# electricals_with_iPod_v2_6.net
KiCad netlist of a schematic drawn in EAGLE
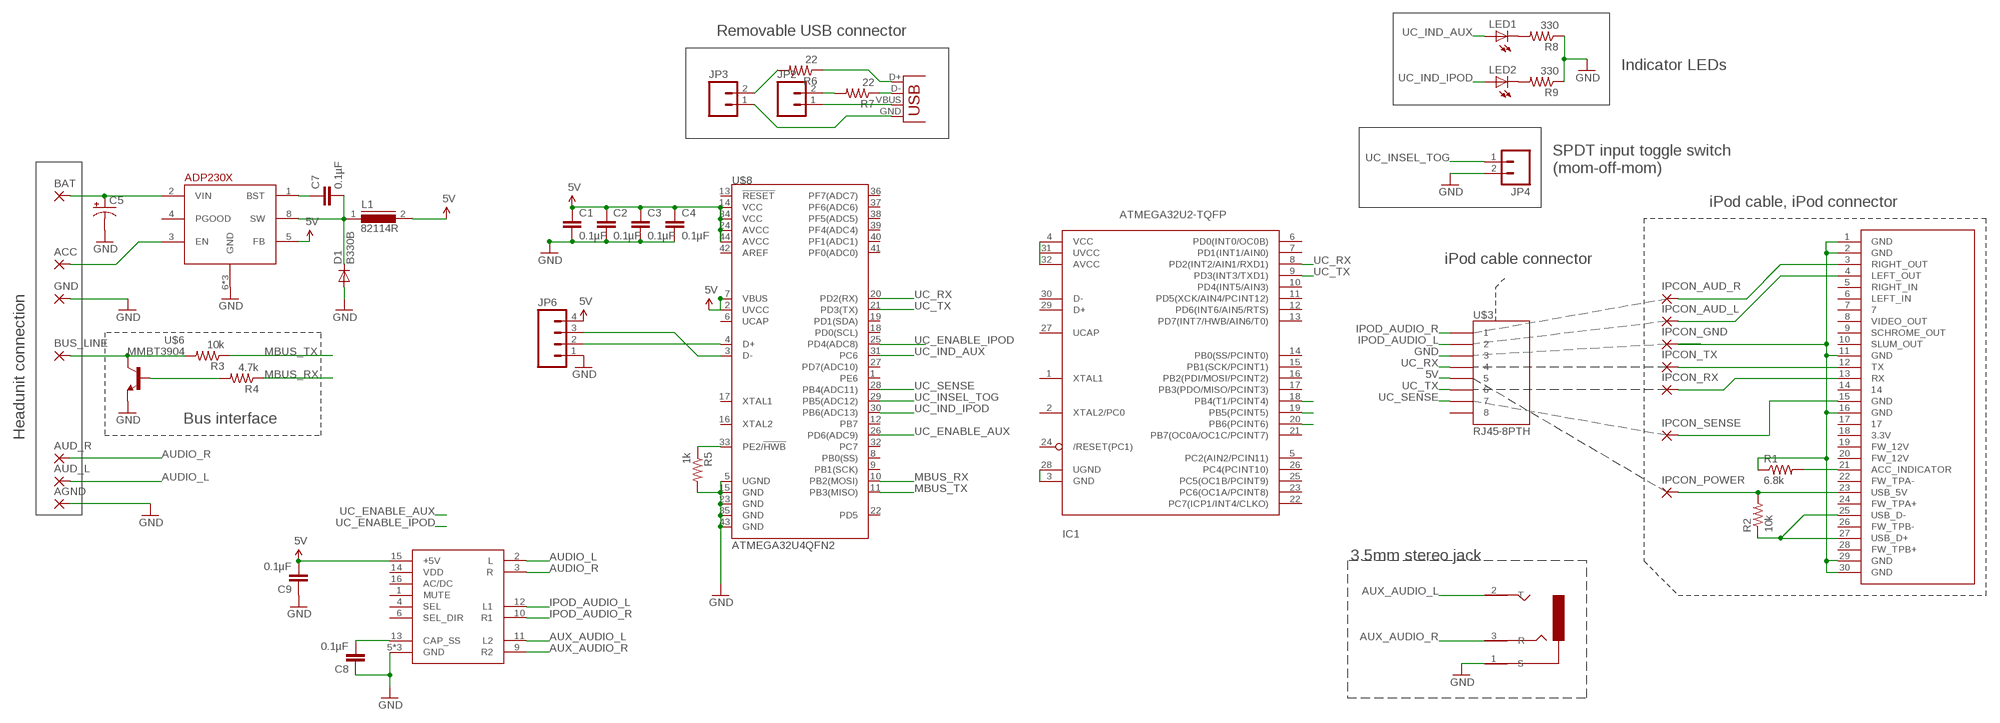
[diagram p0: schematic, sheet 1]

(export (version "E")
  (design (tool "Eeschema 10.0.6"))
  (components
    (comp (ref "ACC")
      (value "1,6/0,9")
      (footprint "eagle-import:1,6_0,9")
      (libsource (lib "eagle-import") (part "1,6/0,9"))
    )
    (comp (ref "AGND")
      (value "1,6/0,9")
      (footprint "eagle-import:1,6_0,9")
      (libsource (lib "eagle-import") (part "1,6/0,9"))
    )
    (comp (ref "AUD_L")
      (value "1,6/0,9")
      (footprint "eagle-import:1,6_0,9")
      (libsource (lib "eagle-import") (part "1,6/0,9"))
    )
    (comp (ref "AUD_R")
      (value "1,6/0,9")
      (footprint "eagle-import:1,6_0,9")
      (libsource (lib "eagle-import") (part "1,6/0,9"))
    )
    (comp (ref "BAT")
      (value "2,54/1,1")
      (footprint "eagle-import:2,54_1,1")
      (libsource (lib "eagle-import") (part "2,54/1,1"))
    )
    (comp (ref "BUS_LINE")
      (value "1,6/0,9")
      (footprint "eagle-import:1,6_0,9")
      (libsource (lib "eagle-import") (part "1,6/0,9"))
    )
    (comp (ref "C1")
      (value "0.1µF")
      (footprint "eagle-import:0603-CAP")
      (libsource (lib "eagle-import") (part "CAP0603-CAP"))
    )
    (comp (ref "C2")
      (value "0.1µF")
      (footprint "eagle-import:0603-CAP")
      (libsource (lib "eagle-import") (part "CAP0603-CAP"))
    )
    (comp (ref "C3")
      (value "0.1µF")
      (footprint "eagle-import:0603-CAP")
      (libsource (lib "eagle-import") (part "CAP0603-CAP"))
    )
    (comp (ref "C4")
      (value "0.1µF")
      (footprint "eagle-import:0603-CAP")
      (libsource (lib "eagle-import") (part "CAP0603-CAP"))
    )
    (comp (ref "C5")
      (value "CAP_POLPTH2")
      (footprint "eagle-import:CPOL-RADIAL-10UF-25V")
      (libsource (lib "eagle-import") (part "CAP_POLPTH2"))
    )
    (comp (ref "C7")
      (value "0.1µF")
      (footprint "eagle-import:0603-CAP")
      (libsource (lib "eagle-import") (part "CAP0603-CAP"))
    )
    (comp (ref "C8")
      (value "0.1µF")
      (footprint "eagle-import:0603-CAP")
      (libsource (lib "eagle-import") (part "CAP0603-CAP"))
    )
    (comp (ref "C9")
      (value "0.1µF")
      (footprint "eagle-import:0603-CAP")
      (libsource (lib "eagle-import") (part "CAP0603-CAP"))
    )
    (comp (ref "D1")
      (value "B330B")
      (footprint "eagle-import:SMA-DIODE_ALT")
      (libsource (lib "eagle-import") (part "DIODESMA-ALT"))
    )
    (comp (ref "GND")
      (value "2,54/1,1")
      (footprint "eagle-import:2,54_1,1")
      (libsource (lib "eagle-import") (part "2,54/1,1"))
    )
    (comp (ref "IC1")
      (value "ATMEGA32U2-TQFP")
      (footprint "eagle-import:TQFP32-08")
      (libsource (lib "eagle-import") (part "ATMEGA32U2-TQFP"))
    )
    (comp (ref "IPCON_AUD_L")
      (value "1,6/0,9")
      (footprint "eagle-import:1,6_0,9")
      (libsource (lib "eagle-import") (part "1,6/0,9"))
    )
    (comp (ref "IPCON_AUD_R")
      (value "1,6/0,9")
      (footprint "eagle-import:1,6_0,9")
      (libsource (lib "eagle-import") (part "1,6/0,9"))
    )
    (comp (ref "IPCON_GND")
      (value "1,6/0,9")
      (footprint "eagle-import:1,6_0,9")
      (libsource (lib "eagle-import") (part "1,6/0,9"))
    )
    (comp (ref "IPCON_POWER")
      (value "1,6/0,9")
      (footprint "eagle-import:1,6_0,9")
      (libsource (lib "eagle-import") (part "1,6/0,9"))
    )
    (comp (ref "IPCON_RX")
      (value "1,6/0,9")
      (footprint "eagle-import:1,6_0,9")
      (libsource (lib "eagle-import") (part "1,6/0,9"))
    )
    (comp (ref "IPCON_SENSE")
      (value "1,6/0,9")
      (footprint "eagle-import:1,6_0,9")
      (libsource (lib "eagle-import") (part "1,6/0,9"))
    )
    (comp (ref "IPCON_TX")
      (value "1,6/0,9")
      (footprint "eagle-import:1,6_0,9")
      (libsource (lib "eagle-import") (part "1,6/0,9"))
    )
    (comp (ref "JP1")
      (value "USBSMD")
      (footprint "eagle-import:USB-MINIB")
      (libsource (lib "eagle-import") (part "USBSMD"))
    )
    (comp (ref "JP2")
      (value "M02POGO_PIN_HOLES_ONLY")
      (footprint "eagle-import:1X02_PP_HOLES_ONLY")
      (libsource (lib "eagle-import") (part "M02POGO_PIN_HOLES_ONLY"))
    )
    (comp (ref "JP3")
      (value "M02POGO_PIN_HOLES_ONLY")
      (footprint "eagle-import:1X02_PP_HOLES_ONLY")
      (libsource (lib "eagle-import") (part "M02POGO_PIN_HOLES_ONLY"))
    )
    (comp (ref "JP4")
      (value "M02LOCK")
      (footprint "eagle-import:1X02_LOCK")
      (libsource (lib "eagle-import") (part "M02LOCK"))
    )
    (comp (ref "JP6")
      (value "M04PTH")
      (footprint "eagle-import:1X04")
      (libsource (lib "eagle-import") (part "M04PTH"))
    )
    (comp (ref "L1")
      (value "82114R")
      (footprint "eagle-import:82114R")
      (libsource (lib "eagle-import") (part "82114R"))
    )
    (comp (ref "LED1")
      (value "LED0603")
      (footprint "eagle-import:LED-0603")
      (libsource (lib "eagle-import") (part "LED0603"))
    )
    (comp (ref "LED2")
      (value "LED0603")
      (footprint "eagle-import:LED-0603")
      (libsource (lib "eagle-import") (part "LED0603"))
    )
    (comp (ref "R1")
      (value "6.8k")
      (footprint "eagle-import:0603-RES")
      (libsource (lib "eagle-import") (part "RESISTOR0603-RES"))
    )
    (comp (ref "R2")
      (value "10k")
      (footprint "eagle-import:0603-RES")
      (libsource (lib "eagle-import") (part "RESISTOR0603-RES"))
    )
    (comp (ref "R3")
      (value "10k")
      (footprint "eagle-import:0603-RES")
      (libsource (lib "eagle-import") (part "RESISTOR0603-RES"))
    )
    (comp (ref "R4")
      (value "4.7k")
      (footprint "eagle-import:0603-RES")
      (libsource (lib "eagle-import") (part "RESISTOR0603-RES"))
    )
    (comp (ref "R5")
      (value "1k")
      (footprint "eagle-import:0603-RES")
      (libsource (lib "eagle-import") (part "RESISTOR0603-RES"))
    )
    (comp (ref "R6")
      (value "22")
      (footprint "eagle-import:0603-RES")
      (libsource (lib "eagle-import") (part "RESISTOR0603-RES"))
    )
    (comp (ref "R7")
      (value "22")
      (footprint "eagle-import:0603-RES")
      (libsource (lib "eagle-import") (part "RESISTOR0603-RES"))
    )
    (comp (ref "R8")
      (value "330")
      (footprint "eagle-import:0603-RES")
      (libsource (lib "eagle-import") (part "RESISTOR0603-RES"))
    )
    (comp (ref "R9")
      (value "330")
      (footprint "eagle-import:0603-RES")
      (libsource (lib "eagle-import") (part "RESISTOR0603-RES"))
    )
    (comp (ref "U$1")
      (value "IPOD_CONNECTOR_MALE")
      (footprint "eagle-import:IPOD_MALE_CONNECTOR")
      (libsource (lib "eagle-import") (part "IPOD_CONNECTOR_MALE"))
    )
    (comp (ref "U$3")
      (value "RJ45-8PTH")
      (footprint "eagle-import:RJ45-8")
      (libsource (lib "eagle-import") (part "RJ45-8PTH"))
    )
    (comp (ref "U$5")
      (value "ADP230X")
      (footprint "eagle-import:SO8-THERM")
      (libsource (lib "eagle-import") (part "ADP230X"))
    )
    (comp (ref "U$6")
      (value "MMBT3904")
      (footprint "eagle-import:SOT23-3")
      (libsource (lib "eagle-import") (part "MMBT3904"))
    )
    (comp (ref "U$7")
      (value "STEREO_JACK_SJ1-353XNG3NG")
      (footprint "eagle-import:3.5MM_SJ1-353XNG")
      (libsource (lib "eagle-import") (part "STEREO_JACK_SJ1-353XNG3NG"))
    )
    (comp (ref "U$8")
      (value "ATMEGA32U4QFN2")
      (footprint "eagle-import:SPARKFUN-DIGITALIC_QFN-44-NOPAD")
      (libsource (lib "eagle-import") (part "ATMEGA32U4QFN2"))
    )
    (comp (ref "U$11")
      (value "ISL54405IRTZ")
      (footprint "eagle-import:QFN-16")
      (libsource (lib "eagle-import") (part "ISL54405IRTZ"))
    )
  )
  (nets
    (net (code "1") (name "/AUDIO_L") (class "Default")
      (node (ref "AUD_L") (pin "1") (pinfunction "P_1") (pintype "passive"))
      (node (ref "U$11") (pin "2") (pinfunction "L_2") (pintype "bidirectional"))
    )
    (net (code "2") (name "/AUDIO_R") (class "Default")
      (node (ref "AUD_R") (pin "1") (pinfunction "P_1") (pintype "passive"))
      (node (ref "U$11") (pin "3") (pinfunction "R_3") (pintype "bidirectional"))
    )
    (net (code "3") (name "/AUX_AUDIO_L") (class "Default")
      (node (ref "U$11") (pin "11") (pinfunction "L2_11") (pintype "bidirectional"))
      (node (ref "U$7") (pin "2") (pinfunction "T_2") (pintype "passive"))
    )
    (net (code "4") (name "/AUX_AUDIO_R") (class "Default")
      (node (ref "U$11") (pin "9") (pinfunction "R2_9") (pintype "bidirectional"))
      (node (ref "U$7") (pin "3") (pinfunction "R_3") (pintype "passive"))
    )
    (net (code "5") (name "/IPOD_AUDIO_L") (class "Default")
      (node (ref "U$11") (pin "12") (pinfunction "L1_12") (pintype "bidirectional"))
      (node (ref "U$3") (pin "2") (pinfunction "2_2") (pintype "bidirectional"))
    )
    (net (code "6") (name "/IPOD_AUDIO_R") (class "Default")
      (node (ref "U$11") (pin "10") (pinfunction "R1_10") (pintype "bidirectional"))
      (node (ref "U$3") (pin "1") (pinfunction "1_1") (pintype "bidirectional"))
    )
    (net (code "7") (name "/MBUS_RX") (class "Default")
      (node (ref "R4") (pin "1") (pinfunction "1_1") (pintype "passive"))
      (node (ref "U$8") (pin "10") (pinfunction "PB2(MOSI)_10") (pintype "bidirectional"))
    )
    (net (code "8") (name "/MBUS_TX") (class "Default")
      (node (ref "R3") (pin "1") (pinfunction "1_1") (pintype "passive"))
      (node (ref "U$8") (pin "11") (pinfunction "PB3(MISO)_11") (pintype "bidirectional"))
    )
    (net (code "9") (name "/UC_ENABLE_AUX") (class "Default")
      (node (ref "U$8") (pin "26") (pinfunction "PD6(ADC9)_26") (pintype "bidirectional"))
    )
    (net (code "10") (name "/UC_ENABLE_IPOD") (class "Default")
      (node (ref "U$8") (pin "25") (pinfunction "PD4(ADC8)_25") (pintype "bidirectional"))
    )
    (net (code "11") (name "/UC_IND_AUX") (class "Default")
      (node (ref "LED1") (pin "A") (pinfunction "A_A") (pintype "passive"))
      (node (ref "U$8") (pin "31") (pinfunction "PC6_31") (pintype "bidirectional"))
    )
    (net (code "12") (name "/UC_IND_IPOD") (class "Default")
      (node (ref "LED2") (pin "A") (pinfunction "A_A") (pintype "passive"))
      (node (ref "U$8") (pin "30") (pinfunction "PB6(ADC13)_30") (pintype "bidirectional"))
    )
    (net (code "13") (name "/UC_INSEL_TOG") (class "Default")
      (node (ref "JP4") (pin "1") (pinfunction "1_1") (pintype "passive"))
      (node (ref "U$8") (pin "29") (pinfunction "PB5(ADC12)_29") (pintype "bidirectional"))
    )
    (net (code "14") (name "/UC_RX") (class "Default")
      (node (ref "IC1") (pin "8") (pinfunction "PD2(INT2/AIN1/RXD1)_8") (pintype "bidirectional"))
      (node (ref "U$3") (pin "4") (pinfunction "4_4") (pintype "bidirectional"))
      (node (ref "U$8") (pin "20") (pinfunction "PD2(RX)_20") (pintype "bidirectional"))
    )
    (net (code "15") (name "/UC_SENSE") (class "Default")
      (node (ref "U$3") (pin "7") (pinfunction "7_7") (pintype "bidirectional"))
      (node (ref "U$8") (pin "28") (pinfunction "PB4(ADC11)_28") (pintype "bidirectional"))
    )
    (net (code "16") (name "/UC_TX") (class "Default")
      (node (ref "IC1") (pin "9") (pinfunction "PD3(INT3/TXD1)_9") (pintype "bidirectional"))
      (node (ref "U$3") (pin "6") (pinfunction "6_6") (pintype "bidirectional"))
      (node (ref "U$8") (pin "21") (pinfunction "PD3(TX)_21") (pintype "bidirectional"))
    )
    (net (code "17") (name "5V") (class "Default")
      (node (ref "C1") (pin "1") (pinfunction "1_1") (pintype "passive"))
      (node (ref "C2") (pin "1") (pinfunction "1_1") (pintype "passive"))
      (node (ref "C3") (pin "1") (pinfunction "1_1") (pintype "passive"))
      (node (ref "C4") (pin "1") (pinfunction "1_1") (pintype "passive"))
      (node (ref "C9") (pin "2") (pinfunction "2_2") (pintype "passive"))
      (node (ref "JP6") (pin "4") (pinfunction "4_4") (pintype "passive"))
      (node (ref "L1") (pin "2") (pinfunction "2_2") (pintype "passive"))
      (node (ref "U$11") (pin "15") (pinfunction "+5V_15") (pintype "bidirectional"))
      (node (ref "U$3") (pin "5") (pinfunction "5_5") (pintype "bidirectional"))
      (node (ref "U$5") (pin "5") (pinfunction "FB_5") (pintype "bidirectional"))
      (node (ref "U$8") (pin "14") (pinfunction "VCC_14") (pintype "bidirectional"))
      (node (ref "U$8") (pin "2") (pinfunction "UVCC_2") (pintype "bidirectional"))
      (node (ref "U$8") (pin "24") (pinfunction "AVCC_24") (pintype "bidirectional"))
      (node (ref "U$8") (pin "34") (pinfunction "VCC_34") (pintype "bidirectional"))
      (node (ref "U$8") (pin "44") (pinfunction "AVCC_44") (pintype "bidirectional"))
      (node (ref "U$8") (pin "7") (pinfunction "VBUS_7") (pintype "bidirectional"))
    )
    (net (code "18") (name "GND") (class "Default")
      (node (ref "AGND") (pin "1") (pinfunction "P_1") (pintype "passive"))
      (node (ref "C1") (pin "2") (pinfunction "2_2") (pintype "passive"))
      (node (ref "C2") (pin "2") (pinfunction "2_2") (pintype "passive"))
      (node (ref "C3") (pin "2") (pinfunction "2_2") (pintype "passive"))
      (node (ref "C4") (pin "2") (pinfunction "2_2") (pintype "passive"))
      (node (ref "C5") (pin "2") (pinfunction "-_2") (pintype "passive"))
      (node (ref "C8") (pin "1") (pinfunction "1_1") (pintype "passive"))
      (node (ref "C9") (pin "1") (pinfunction "1_1") (pintype "passive"))
      (node (ref "D1") (pin "A") (pinfunction "A_A") (pintype "passive"))
      (node (ref "GND") (pin "1") (pinfunction "P_1") (pintype "passive"))
      (node (ref "JP4") (pin "2") (pinfunction "2_2") (pintype "passive"))
      (node (ref "JP6") (pin "1") (pinfunction "1_1") (pintype "passive"))
      (node (ref "R5") (pin "2") (pinfunction "2_2") (pintype "passive"))
      (node (ref "R8") (pin "1") (pinfunction "1_1") (pintype "passive"))
      (node (ref "R9") (pin "1") (pinfunction "1_1") (pintype "passive"))
      (node (ref "U$11") (pin "5") (pinfunction "GND_5") (pintype "bidirectional"))
      (node (ref "U$11") (pin "7") (pinfunction "GND_7") (pintype "bidirectional"))
      (node (ref "U$11") (pin "8") (pinfunction "GND_8") (pintype "bidirectional"))
      (node (ref "U$3") (pin "3") (pinfunction "3_3") (pintype "bidirectional"))
      (node (ref "U$5") (pin "6") (pinfunction "GND_6") (pintype "bidirectional"))
      (node (ref "U$5") (pin "7") (pinfunction "GND_7") (pintype "bidirectional"))
      (node (ref "U$5") (pin "PAD") (pinfunction "GND_PAD") (pintype "bidirectional"))
      (node (ref "U$6") (pin "2") (pinfunction "E_2") (pintype "passive"))
      (node (ref "U$7") (pin "1") (pinfunction "S_1") (pintype "passive"))
      (node (ref "U$8") (pin "15") (pinfunction "GND_15") (pintype "bidirectional"))
      (node (ref "U$8") (pin "23") (pinfunction "GND_23") (pintype "bidirectional"))
      (node (ref "U$8") (pin "35") (pinfunction "GND_35") (pintype "bidirectional"))
      (node (ref "U$8") (pin "43") (pinfunction "GND_43") (pintype "bidirectional"))
      (node (ref "U$8") (pin "5") (pinfunction "UGND_5") (pintype "bidirectional"))
    )
    (net (code "19") (name "Net-(ACC-P)") (class "Default")
      (node (ref "ACC") (pin "1") (pinfunction "P_1") (pintype "passive"))
      (node (ref "U$5") (pin "3") (pinfunction "EN_3") (pintype "bidirectional"))
    )
    (net (code "20") (name "Net-(BAT-P)") (class "Default")
      (node (ref "BAT") (pin "1") (pinfunction "P_1") (pintype "passive"))
      (node (ref "C5") (pin "1") (pinfunction "+_1") (pintype "passive"))
      (node (ref "U$5") (pin "2") (pinfunction "VIN_2") (pintype "bidirectional"))
    )
    (net (code "21") (name "Net-(BUS_LINE-P)") (class "Default")
      (node (ref "BUS_LINE") (pin "1") (pinfunction "P_1") (pintype "passive"))
      (node (ref "R3") (pin "2") (pinfunction "2_2") (pintype "passive"))
      (node (ref "U$6") (pin "3") (pinfunction "C_3") (pintype "passive"))
    )
    (net (code "22") (name "Net-(IC1-AVCC)") (class "Default")
      (node (ref "IC1") (pin "32") (pinfunction "AVCC_32") (pintype "bidirectional"))
      (node (ref "IC1") (pin "4") (pinfunction "VCC_4") (pintype "bidirectional"))
    )
    (net (code "23") (name "Net-(IC1-GND)") (class "Default")
      (node (ref "IC1") (pin "28") (pinfunction "UGND_28") (pintype "bidirectional"))
      (node (ref "IC1") (pin "3") (pinfunction "GND_3") (pintype "bidirectional"))
    )
    (net (code "24") (name "Net-(IPCON_AUD_L-P)") (class "Default")
      (node (ref "IPCON_AUD_L") (pin "1") (pinfunction "P_1") (pintype "passive"))
      (node (ref "U$1") (pin "4") (pinfunction "LEFT_OUT_4") (pintype "bidirectional"))
    )
    (net (code "25") (name "Net-(IPCON_AUD_R-P)") (class "Default")
      (node (ref "IPCON_AUD_R") (pin "1") (pinfunction "P_1") (pintype "passive"))
      (node (ref "U$1") (pin "3") (pinfunction "RIGHT_OUT_3") (pintype "bidirectional"))
    )
    (net (code "26") (name "Net-(IPCON_GND-P)") (class "Default")
      (node (ref "IPCON_GND") (pin "1") (pinfunction "P_1") (pintype "passive"))
      (node (ref "R1") (pin "1") (pinfunction "1_1") (pintype "passive"))
      (node (ref "U$1") (pin "1") (pinfunction "GND_1") (pintype "bidirectional"))
      (node (ref "U$1") (pin "11") (pinfunction "GND_11") (pintype "bidirectional"))
      (node (ref "U$1") (pin "16") (pinfunction "GND_16") (pintype "bidirectional"))
      (node (ref "U$1") (pin "2") (pinfunction "GND_2") (pintype "bidirectional"))
      (node (ref "U$1") (pin "29") (pinfunction "GND_29") (pintype "bidirectional"))
      (node (ref "U$1") (pin "30") (pinfunction "GND_30") (pintype "bidirectional"))
    )
    (net (code "27") (name "Net-(IPCON_POWER-P)") (class "Default")
      (node (ref "IPCON_POWER") (pin "1") (pinfunction "P_1") (pintype "passive"))
      (node (ref "R2") (pin "2") (pinfunction "2_2") (pintype "passive"))
      (node (ref "U$1") (pin "23") (pinfunction "USB_5V_23") (pintype "bidirectional"))
    )
    (net (code "28") (name "Net-(IPCON_RX-P)") (class "Default")
      (node (ref "IPCON_RX") (pin "1") (pinfunction "P_1") (pintype "passive"))
      (node (ref "U$1") (pin "13") (pinfunction "RX_13") (pintype "bidirectional"))
    )
    (net (code "29") (name "Net-(IPCON_SENSE-P)") (class "Default")
      (node (ref "IPCON_SENSE") (pin "1") (pinfunction "P_1") (pintype "passive"))
      (node (ref "U$1") (pin "15") (pinfunction "GND_15") (pintype "bidirectional"))
    )
    (net (code "30") (name "Net-(IPCON_TX-P)") (class "Default")
      (node (ref "IPCON_TX") (pin "1") (pinfunction "P_1") (pintype "passive"))
      (node (ref "U$1") (pin "12") (pinfunction "TX_12") (pintype "bidirectional"))
    )
    (net (code "31") (name "Net-(JP1-PadD+)") (class "Default")
      (node (ref "JP1") (pin "D+") (pinfunction "D+_D+") (pintype "bidirectional"))
      (node (ref "R6") (pin "1") (pinfunction "1_1") (pintype "passive"))
    )
    (net (code "32") (name "Net-(JP1-PadD-)") (class "Default")
      (node (ref "JP1") (pin "D-") (pinfunction "D-_D-") (pintype "bidirectional"))
      (node (ref "R7") (pin "1") (pinfunction "1_1") (pintype "passive"))
    )
    (net (code "33") (name "Net-(JP1-PadGND)") (class "Default")
      (node (ref "JP1") (pin "GND") (pinfunction "GND_GND") (pintype "bidirectional"))
      (node (ref "JP3") (pin "1") (pinfunction "1_1") (pintype "passive"))
    )
    (net (code "34") (name "Net-(JP1-PadVBUS)") (class "Default")
      (node (ref "JP1") (pin "VBUS") (pinfunction "VBUS_VBUS") (pintype "bidirectional"))
      (node (ref "JP2") (pin "1") (pinfunction "1_1") (pintype "passive"))
    )
    (net (code "35") (name "Net-(JP2-Pad2)") (class "Default")
      (node (ref "JP2") (pin "2") (pinfunction "2_2") (pintype "passive"))
      (node (ref "R7") (pin "2") (pinfunction "2_2") (pintype "passive"))
    )
    (net (code "36") (name "Net-(JP3-Pad2)") (class "Default")
      (node (ref "JP3") (pin "2") (pinfunction "2_2") (pintype "passive"))
      (node (ref "R6") (pin "2") (pinfunction "2_2") (pintype "passive"))
    )
    (net (code "37") (name "Net-(LED1-PadC)") (class "Default")
      (node (ref "LED1") (pin "C") (pinfunction "C_C") (pintype "passive"))
      (node (ref "R8") (pin "2") (pinfunction "2_2") (pintype "passive"))
    )
    (net (code "38") (name "Net-(LED2-PadC)") (class "Default")
      (node (ref "LED2") (pin "C") (pinfunction "C_C") (pintype "passive"))
      (node (ref "R9") (pin "2") (pinfunction "2_2") (pintype "passive"))
    )
    (net (code "39") (name "Net-(U$1-ACC_INDICATOR)") (class "Default")
      (node (ref "R1") (pin "2") (pinfunction "2_2") (pintype "passive"))
      (node (ref "U$1") (pin "21") (pinfunction "ACC_INDICATOR_21") (pintype "bidirectional"))
    )
    (net (code "40") (name "Net-(U$1-USB_D+)") (class "Default")
      (node (ref "R2") (pin "1") (pinfunction "1_1") (pintype "passive"))
      (node (ref "U$1") (pin "25") (pinfunction "USB_D-_25") (pintype "bidirectional"))
      (node (ref "U$1") (pin "27") (pinfunction "USB_D+_27") (pintype "bidirectional"))
    )
    (net (code "41") (name "Net-(U$5-BST)") (class "Default")
      (node (ref "C7") (pin "1") (pinfunction "1_1") (pintype "passive"))
      (node (ref "U$5") (pin "1") (pinfunction "BST_1") (pintype "bidirectional"))
    )
    (net (code "42") (name "Net-(U$5-SW)") (class "Default")
      (node (ref "C7") (pin "2") (pinfunction "2_2") (pintype "passive"))
      (node (ref "D1") (pin "C") (pinfunction "C_C") (pintype "passive"))
      (node (ref "L1") (pin "1") (pinfunction "1_1") (pintype "passive"))
      (node (ref "U$5") (pin "8") (pinfunction "SW_8") (pintype "bidirectional"))
    )
    (net (code "43") (name "Net-(U$6-B)") (class "Default")
      (node (ref "R4") (pin "2") (pinfunction "2_2") (pintype "passive"))
      (node (ref "U$6") (pin "1") (pinfunction "B_1") (pintype "passive"))
    )
    (net (code "44") (name "Net-(U$8-D+)") (class "Default")
      (node (ref "JP6") (pin "2") (pinfunction "2_2") (pintype "passive"))
      (node (ref "U$8") (pin "4") (pinfunction "D+_4") (pintype "bidirectional"))
    )
    (net (code "45") (name "Net-(U$8-D-)") (class "Default")
      (node (ref "JP6") (pin "3") (pinfunction "3_3") (pintype "passive"))
      (node (ref "U$8") (pin "3") (pinfunction "D-_3") (pintype "bidirectional"))
    )
    (net (code "46") (name "Net-(U$8-PE2{slash}~{HWB})") (class "Default")
      (node (ref "R5") (pin "1") (pinfunction "1_1") (pintype "passive"))
      (node (ref "U$8") (pin "33") (pinfunction "PE2/~{HWB}_33") (pintype "bidirectional"))
    )
    (net (code "47") (name "Net-(U$11-CAP_SS)") (class "Default")
      (node (ref "C8") (pin "2") (pinfunction "2_2") (pintype "passive"))
      (node (ref "U$11") (pin "13") (pinfunction "CAP_SS_13") (pintype "bidirectional"))
    )
    (net (code "48") (name "unconnected-(IC1-D+-Pad29)") (class "Default")
      (node (ref "IC1") (pin "29") (pinfunction "D+_29") (pintype "bidirectional"))
    )
    (net (code "49") (name "unconnected-(IC1-D--Pad30)") (class "Default")
      (node (ref "IC1") (pin "30") (pinfunction "D-_30") (pintype "bidirectional"))
    )
    (net (code "50") (name "unconnected-(IC1-PB0(SS{slash}PCINT0)-Pad14)") (class "Default")
      (node (ref "IC1") (pin "14") (pinfunction "PB0(SS/PCINT0)_14") (pintype "bidirectional"))
    )
    (net (code "51") (name "unconnected-(IC1-PB1(SCK{slash}PCINT1)-Pad15)") (class "Default")
      (node (ref "IC1") (pin "15") (pinfunction "PB1(SCK/PCINT1)_15") (pintype "bidirectional"))
    )
    (net (code "52") (name "unconnected-(IC1-PB2(PDI{slash}MOSI{slash}PCINT2)-Pad16)") (class "Default")
      (node (ref "IC1") (pin "16") (pinfunction "PB2(PDI/MOSI/PCINT2)_16") (pintype "bidirectional"))
    )
    (net (code "53") (name "unconnected-(IC1-PB3(PDO{slash}MISO{slash}PCINT3)-Pad17)") (class "Default")
      (node (ref "IC1") (pin "17") (pinfunction "PB3(PDO/MISO/PCINT3)_17") (pintype "bidirectional"))
    )
    (net (code "54") (name "unconnected-(IC1-PB4(T1{slash}PCINT4)-Pad18)") (class "Default")
      (node (ref "IC1") (pin "18") (pinfunction "PB4(T1/PCINT4)_18") (pintype "bidirectional"))
    )
    (net (code "55") (name "unconnected-(IC1-PB5(PCINT5)-Pad19)") (class "Default")
      (node (ref "IC1") (pin "19") (pinfunction "PB5(PCINT5)_19") (pintype "bidirectional"))
    )
    (net (code "56") (name "unconnected-(IC1-PB6(PCINT6)-Pad20)") (class "Default")
      (node (ref "IC1") (pin "20") (pinfunction "PB6(PCINT6)_20") (pintype "bidirectional"))
    )
    (net (code "57") (name "unconnected-(IC1-PB7(OC0A{slash}OC1C{slash}PCINT7)-Pad21)") (class "Default")
      (node (ref "IC1") (pin "21") (pinfunction "PB7(OC0A/OC1C/PCINT7)_21") (pintype "bidirectional"))
    )
    (net (code "58") (name "unconnected-(IC1-PC2(AIN2{slash}PCIN11)-Pad5)") (class "Default")
      (node (ref "IC1") (pin "5") (pinfunction "PC2(AIN2/PCIN11)_5") (pintype "bidirectional"))
    )
    (net (code "59") (name "unconnected-(IC1-PC4(PCINT10)-Pad26)") (class "Default")
      (node (ref "IC1") (pin "26") (pinfunction "PC4(PCINT10)_26") (pintype "bidirectional"))
    )
    (net (code "60") (name "unconnected-(IC1-PC5(OC1B{slash}PCINT9)-Pad25)") (class "Default")
      (node (ref "IC1") (pin "25") (pinfunction "PC5(OC1B/PCINT9)_25") (pintype "bidirectional"))
    )
    (net (code "61") (name "unconnected-(IC1-PC6(OC1A{slash}PCINT8)-Pad23)") (class "Default")
      (node (ref "IC1") (pin "23") (pinfunction "PC6(OC1A/PCINT8)_23") (pintype "bidirectional"))
    )
    (net (code "62") (name "unconnected-(IC1-PC7(ICP1{slash}INT4{slash}CLKO)-Pad22)") (class "Default")
      (node (ref "IC1") (pin "22") (pinfunction "PC7(ICP1/INT4/CLKO)_22") (pintype "bidirectional"))
    )
    (net (code "63") (name "unconnected-(IC1-PD0(INT0{slash}OC0B)-Pad6)") (class "Default")
      (node (ref "IC1") (pin "6") (pinfunction "PD0(INT0/OC0B)_6") (pintype "bidirectional"))
    )
    (net (code "64") (name "unconnected-(IC1-PD1(INT1{slash}AIN0)-Pad7)") (class "Default")
      (node (ref "IC1") (pin "7") (pinfunction "PD1(INT1/AIN0)_7") (pintype "bidirectional"))
    )
    (net (code "65") (name "unconnected-(IC1-PD4(INT5{slash}AIN3)-Pad10)") (class "Default")
      (node (ref "IC1") (pin "10") (pinfunction "PD4(INT5/AIN3)_10") (pintype "bidirectional"))
    )
    (net (code "66") (name "unconnected-(IC1-PD5(XCK{slash}AIN4{slash}PCINT12)-Pad11)") (class "Default")
      (node (ref "IC1") (pin "11") (pinfunction "PD5(XCK/AIN4/PCINT12)_11") (pintype "bidirectional"))
    )
    (net (code "67") (name "unconnected-(IC1-PD6(INT6{slash}AIN5{slash}RTS)-Pad12)") (class "Default")
      (node (ref "IC1") (pin "12") (pinfunction "PD6(INT6/AIN5/RTS)_12") (pintype "bidirectional"))
    )
    (net (code "68") (name "unconnected-(IC1-PD7(INT7{slash}HWB{slash}AIN6{slash}T0)-Pad13)") (class "Default")
      (node (ref "IC1") (pin "13") (pinfunction "PD7(INT7/HWB/AIN6/T0)_13") (pintype "bidirectional"))
    )
    (net (code "69") (name "unconnected-(IC1-UCAP-Pad27)") (class "Default")
      (node (ref "IC1") (pin "27") (pinfunction "UCAP_27") (pintype "bidirectional"))
    )
    (net (code "70") (name "unconnected-(IC1-UVCC-Pad31)") (class "Default")
      (node (ref "IC1") (pin "31") (pinfunction "UVCC_31") (pintype "bidirectional"))
    )
    (net (code "71") (name "unconnected-(IC1-XTAL1-Pad1)") (class "Default")
      (node (ref "IC1") (pin "1") (pinfunction "XTAL1_1") (pintype "bidirectional"))
    )
    (net (code "72") (name "unconnected-(IC1-XTAL2{slash}PC0-Pad2)") (class "Default")
      (node (ref "IC1") (pin "2") (pinfunction "XTAL2/PC0_2") (pintype "bidirectional"))
    )
    (net (code "73") (name "unconnected-(IC1-{slash}RESET(PC1)-Pad24)") (class "Default")
      (node (ref "IC1") (pin "24") (pinfunction "/RESET(PC1)_24") (pintype "bidirectional"))
    )
    (net (code "74") (name "unconnected-(U$1-3.3V-Pad18)") (class "Default")
      (node (ref "U$1") (pin "18") (pinfunction "3.3V_18") (pintype "bidirectional"))
    )
    (net (code "75") (name "unconnected-(U$1-FW_12V-Pad19)") (class "Default")
      (node (ref "U$1") (pin "19") (pinfunction "FW_12V_19") (pintype "bidirectional"))
    )
    (net (code "76") (name "unconnected-(U$1-FW_12V-Pad20)") (class "Default")
      (node (ref "U$1") (pin "20") (pinfunction "FW_12V_20") (pintype "bidirectional"))
    )
    (net (code "77") (name "unconnected-(U$1-FW_TPA+-Pad24)") (class "Default")
      (node (ref "U$1") (pin "24") (pinfunction "FW_TPA+_24") (pintype "bidirectional"))
    )
    (net (code "78") (name "unconnected-(U$1-FW_TPA--Pad22)") (class "Default")
      (node (ref "U$1") (pin "22") (pinfunction "FW_TPA-_22") (pintype "bidirectional"))
    )
    (net (code "79") (name "unconnected-(U$1-FW_TPB+-Pad28)") (class "Default")
      (node (ref "U$1") (pin "28") (pinfunction "FW_TPB+_28") (pintype "bidirectional"))
    )
    (net (code "80") (name "unconnected-(U$1-FW_TPB--Pad26)") (class "Default")
      (node (ref "U$1") (pin "26") (pinfunction "FW_TPB-_26") (pintype "bidirectional"))
    )
    (net (code "81") (name "unconnected-(U$1-LEFT_IN-Pad6)") (class "Default")
      (node (ref "U$1") (pin "6") (pinfunction "LEFT_IN_6") (pintype "bidirectional"))
    )
    (net (code "82") (name "unconnected-(U$1-Pad7)") (class "Default")
      (node (ref "U$1") (pin "7") (pinfunction "7_7") (pintype "bidirectional"))
    )
    (net (code "83") (name "unconnected-(U$1-Pad14)") (class "Default")
      (node (ref "U$1") (pin "14") (pinfunction "14_14") (pintype "bidirectional"))
    )
    (net (code "84") (name "unconnected-(U$1-Pad17)") (class "Default")
      (node (ref "U$1") (pin "17") (pinfunction "17_17") (pintype "bidirectional"))
    )
    (net (code "85") (name "unconnected-(U$1-RIGHT_IN-Pad5)") (class "Default")
      (node (ref "U$1") (pin "5") (pinfunction "RIGHT_IN_5") (pintype "bidirectional"))
    )
    (net (code "86") (name "unconnected-(U$1-SCHROME_OUT-Pad9)") (class "Default")
      (node (ref "U$1") (pin "9") (pinfunction "SCHROME_OUT_9") (pintype "bidirectional"))
    )
    (net (code "87") (name "unconnected-(U$1-SLUM_OUT-Pad10)") (class "Default")
      (node (ref "U$1") (pin "10") (pinfunction "SLUM_OUT_10") (pintype "bidirectional"))
    )
    (net (code "88") (name "unconnected-(U$1-VIDEO_OUT-Pad8)") (class "Default")
      (node (ref "U$1") (pin "8") (pinfunction "VIDEO_OUT_8") (pintype "bidirectional"))
    )
    (net (code "89") (name "unconnected-(U$3-Pad8)") (class "Default")
      (node (ref "U$3") (pin "8") (pinfunction "8_8") (pintype "bidirectional"))
    )
    (net (code "90") (name "unconnected-(U$5-PGOOD-Pad4)") (class "Default")
      (node (ref "U$5") (pin "4") (pinfunction "PGOOD_4") (pintype "bidirectional"))
    )
    (net (code "91") (name "unconnected-(U$8-AREF-Pad42)") (class "Default")
      (node (ref "U$8") (pin "42") (pinfunction "AREF_42") (pintype "bidirectional"))
    )
    (net (code "92") (name "unconnected-(U$8-PB0(SS)-Pad8)") (class "Default")
      (node (ref "U$8") (pin "8") (pinfunction "PB0(SS)_8") (pintype "bidirectional"))
    )
    (net (code "93") (name "unconnected-(U$8-PB1(SCK)-Pad9)") (class "Default")
      (node (ref "U$8") (pin "9") (pinfunction "PB1(SCK)_9") (pintype "bidirectional"))
    )
    (net (code "94") (name "unconnected-(U$8-PB7-Pad12)") (class "Default")
      (node (ref "U$8") (pin "12") (pinfunction "PB7_12") (pintype "bidirectional"))
    )
    (net (code "95") (name "unconnected-(U$8-PC7-Pad32)") (class "Default")
      (node (ref "U$8") (pin "32") (pinfunction "PC7_32") (pintype "bidirectional"))
    )
    (net (code "96") (name "unconnected-(U$8-PD0(SCL)-Pad18)") (class "Default")
      (node (ref "U$8") (pin "18") (pinfunction "PD0(SCL)_18") (pintype "bidirectional"))
    )
    (net (code "97") (name "unconnected-(U$8-PD1(SDA)-Pad19)") (class "Default")
      (node (ref "U$8") (pin "19") (pinfunction "PD1(SDA)_19") (pintype "bidirectional"))
    )
    (net (code "98") (name "unconnected-(U$8-PD5-Pad22)") (class "Default")
      (node (ref "U$8") (pin "22") (pinfunction "PD5_22") (pintype "bidirectional"))
    )
    (net (code "99") (name "unconnected-(U$8-PD7(ADC10)-Pad27)") (class "Default")
      (node (ref "U$8") (pin "27") (pinfunction "PD7(ADC10)_27") (pintype "bidirectional"))
    )
    (net (code "100") (name "unconnected-(U$8-PE6-Pad1)") (class "Default")
      (node (ref "U$8") (pin "1") (pinfunction "PE6_1") (pintype "bidirectional"))
    )
    (net (code "101") (name "unconnected-(U$8-PF0(ADC0)-Pad41)") (class "Default")
      (node (ref "U$8") (pin "41") (pinfunction "PF0(ADC0)_41") (pintype "bidirectional"))
    )
    (net (code "102") (name "unconnected-(U$8-PF1(ADC1)-Pad40)") (class "Default")
      (node (ref "U$8") (pin "40") (pinfunction "PF1(ADC1)_40") (pintype "bidirectional"))
    )
    (net (code "103") (name "unconnected-(U$8-PF4(ADC4)-Pad39)") (class "Default")
      (node (ref "U$8") (pin "39") (pinfunction "PF4(ADC4)_39") (pintype "bidirectional"))
    )
    (net (code "104") (name "unconnected-(U$8-PF5(ADC5)-Pad38)") (class "Default")
      (node (ref "U$8") (pin "38") (pinfunction "PF5(ADC5)_38") (pintype "bidirectional"))
    )
    (net (code "105") (name "unconnected-(U$8-PF6(ADC6)-Pad37)") (class "Default")
      (node (ref "U$8") (pin "37") (pinfunction "PF6(ADC6)_37") (pintype "bidirectional"))
    )
    (net (code "106") (name "unconnected-(U$8-PF7(ADC7)-Pad36)") (class "Default")
      (node (ref "U$8") (pin "36") (pinfunction "PF7(ADC7)_36") (pintype "bidirectional"))
    )
    (net (code "107") (name "unconnected-(U$8-UCAP-Pad6)") (class "Default")
      (node (ref "U$8") (pin "6") (pinfunction "UCAP_6") (pintype "bidirectional"))
    )
    (net (code "108") (name "unconnected-(U$8-XTAL1-Pad17)") (class "Default")
      (node (ref "U$8") (pin "17") (pinfunction "XTAL1_17") (pintype "bidirectional"))
    )
    (net (code "109") (name "unconnected-(U$8-XTAL2-Pad16)") (class "Default")
      (node (ref "U$8") (pin "16") (pinfunction "XTAL2_16") (pintype "bidirectional"))
    )
    (net (code "110") (name "unconnected-(U$8-~{RESET}-Pad13)") (class "Default")
      (node (ref "U$8") (pin "13") (pinfunction "~{RESET}_13") (pintype "bidirectional"))
    )
    (net (code "111") (name "unconnected-(U$11-AC{slash}DC-Pad16)") (class "Default")
      (node (ref "U$11") (pin "16") (pinfunction "AC/DC_16") (pintype "bidirectional"))
    )
    (net (code "112") (name "unconnected-(U$11-MUTE-Pad1)") (class "Default")
      (node (ref "U$11") (pin "1") (pinfunction "MUTE_1") (pintype "bidirectional"))
    )
    (net (code "113") (name "unconnected-(U$11-SEL-Pad4)") (class "Default")
      (node (ref "U$11") (pin "4") (pinfunction "SEL_4") (pintype "bidirectional"))
    )
    (net (code "114") (name "unconnected-(U$11-SEL_DIR-Pad6)") (class "Default")
      (node (ref "U$11") (pin "6") (pinfunction "SEL_DIR_6") (pintype "bidirectional"))
    )
    (net (code "115") (name "unconnected-(U$11-VDD-Pad14)") (class "Default")
      (node (ref "U$11") (pin "14") (pinfunction "VDD_14") (pintype "bidirectional"))
    )
  )
)
